# zero_board.net
KiCad netlist of a schematic drawn in EAGLE
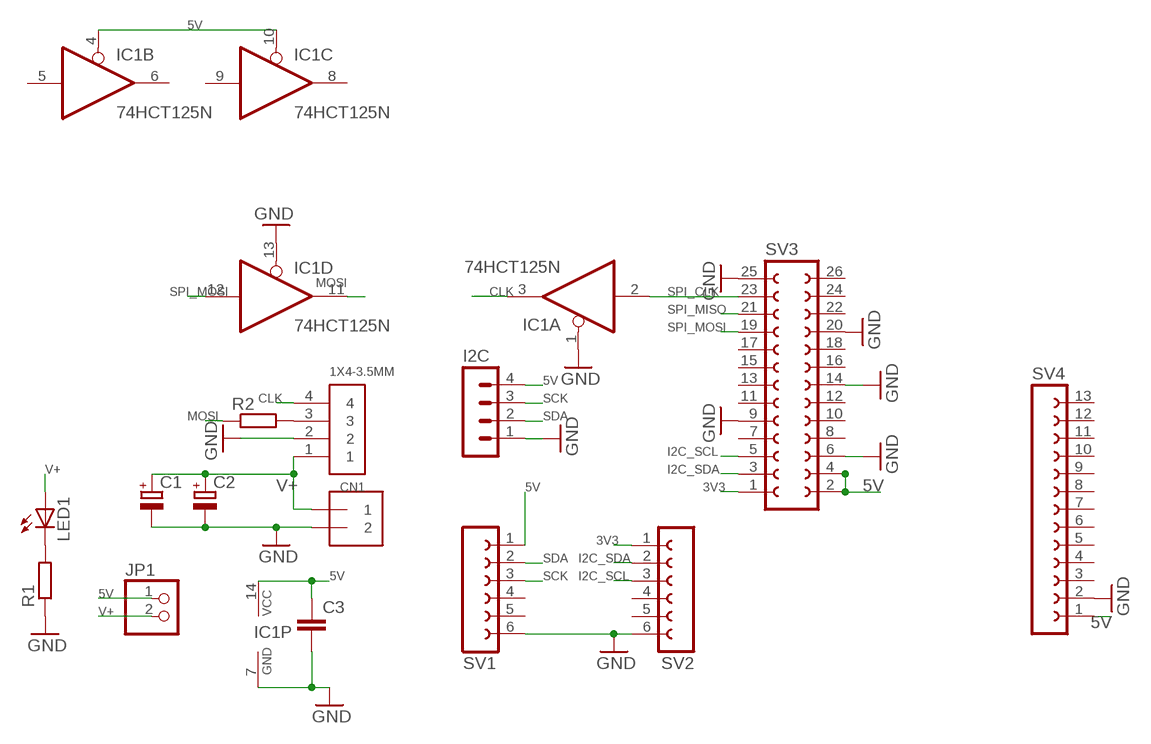
[diagram p0: schematic, sheet 1]

(export (version "E")
  (design (tool "Eeschema 10.0.6"))
  (components
    (comp (ref "C1")
      (value "CPOL-EUE5-6")
      (footprint "eagle-import:E5-6")
      (libsource (lib "eagle-import") (part "CPOL-EUE5-6"))
    )
    (comp (ref "C2")
      (value "CPOL-EUE5-6")
      (footprint "eagle-import:E5-6")
      (libsource (lib "eagle-import") (part "CPOL-EUE5-6"))
    )
    (comp (ref "C3")
      (value "C-EU050-024X044")
      (footprint "eagle-import:C050-024X044")
      (libsource (lib "eagle-import") (part "C-EU050-024X044"))
    )
    (comp (ref "CN1")
      (value "1X4-3.5MM")
      (footprint "eagle-import:1X04-3.5MM")
      (libsource (lib "eagle-import") (part "1X4-3.5MM"))
    )
    (comp (ref "I2C")
      (value "MA04-1")
      (footprint "eagle-import:MA04-1")
      (libsource (lib "eagle-import") (part "MA04-1"))
    )
    (comp (ref "IC1")
      (value "74HCT125N")
      (footprint "eagle-import:DIL14")
      (libsource (lib "eagle-import") (part "74125NHCT"))
    )
    (comp (ref "J1")
      (value "1X2-3.5MM")
      (footprint "eagle-import:1X2-3.5MM")
      (libsource (lib "eagle-import") (part "1X2-3.5MM"))
    )
    (comp (ref "JP1")
      (value "PINHD-1X2")
      (footprint "eagle-import:1X02")
      (libsource (lib "eagle-import") (part "PINHD-1X2"))
    )
    (comp (ref "LED1")
      (value "LED3MM")
      (footprint "eagle-import:LED3MM")
      (libsource (lib "eagle-import") (part "LED3MM"))
    )
    (comp (ref "R1")
      (value "R-EU_0204/5")
      (footprint "eagle-import:0204_5")
      (libsource (lib "eagle-import") (part "R-EU_0204/5"))
    )
    (comp (ref "R2")
      (value "R-EU_0204/5")
      (footprint "eagle-import:0204_5")
      (libsource (lib "eagle-import") (part "R-EU_0204/5"))
    )
    (comp (ref "SV1")
      (value "FE06-1")
      (footprint "eagle-import:FE06")
      (libsource (lib "eagle-import") (part "FE06-1"))
    )
    (comp (ref "SV2")
      (value "FE06-1")
      (footprint "eagle-import:FE06")
      (libsource (lib "eagle-import") (part "FE06-1"))
    )
    (comp (ref "SV3")
      (value "FE13-2")
      (footprint "eagle-import:FE13-2")
      (libsource (lib "eagle-import") (part "FE13-2"))
    )
    (comp (ref "SV4")
      (value "FE13-1")
      (footprint "eagle-import:FE13")
      (libsource (lib "eagle-import") (part "FE13-1"))
    )
  )
  (nets
    (net (code "1") (name "/3V3") (class "Default")
      (node (ref "SV2") (pin "1") (pinfunction "1_1") (pintype "passive"))
      (node (ref "SV3") (pin "1") (pinfunction "1_1") (pintype "passive"))
    )
    (net (code "2") (name "/5V") (class "Default")
      (node (ref "C3") (pin "1") (pinfunction "1_1") (pintype "passive"))
      (node (ref "I2C") (pin "4") (pinfunction "4_4") (pintype "passive"))
      (node (ref "IC1") (pin "10") (pinfunction "OE_10") (pintype "input"))
      (node (ref "IC1") (pin "14") (pinfunction "VCC_14") (pintype "power_in"))
      (node (ref "IC1") (pin "4") (pinfunction "OE_4") (pintype "input"))
      (node (ref "JP1") (pin "1") (pinfunction "1_1") (pintype "passive"))
      (node (ref "SV1") (pin "1") (pinfunction "1_1") (pintype "passive"))
      (node (ref "SV3") (pin "2") (pinfunction "2_2") (pintype "passive"))
      (node (ref "SV3") (pin "4") (pinfunction "4_4") (pintype "passive"))
      (node (ref "SV4") (pin "1") (pinfunction "1_1") (pintype "passive"))
    )
    (net (code "3") (name "/CLK") (class "Default")
      (node (ref "CN1") (pin "4") (pinfunction "4_4") (pintype "bidirectional"))
      (node (ref "IC1") (pin "3") (pinfunction "O_3") (pintype "tri_state"))
    )
    (net (code "4") (name "/I2C_SCL") (class "Default")
      (node (ref "SV2") (pin "3") (pinfunction "3_3") (pintype "passive"))
      (node (ref "SV3") (pin "5") (pinfunction "5_5") (pintype "passive"))
    )
    (net (code "5") (name "/I2C_SDA") (class "Default")
      (node (ref "SV2") (pin "2") (pinfunction "2_2") (pintype "passive"))
      (node (ref "SV3") (pin "3") (pinfunction "3_3") (pintype "passive"))
    )
    (net (code "6") (name "/MOSI") (class "Default")
      (node (ref "IC1") (pin "11") (pinfunction "O_11") (pintype "tri_state"))
      (node (ref "R2") (pin "1") (pinfunction "1_1") (pintype "passive"))
    )
    (net (code "7") (name "/SCK") (class "Default")
      (node (ref "I2C") (pin "3") (pinfunction "3_3") (pintype "passive"))
      (node (ref "SV1") (pin "3") (pinfunction "3_3") (pintype "passive"))
    )
    (net (code "8") (name "/SDA") (class "Default")
      (node (ref "I2C") (pin "2") (pinfunction "2_2") (pintype "passive"))
      (node (ref "SV1") (pin "2") (pinfunction "2_2") (pintype "passive"))
    )
    (net (code "9") (name "/SPI_CLK") (class "Default")
      (node (ref "IC1") (pin "2") (pinfunction "I_2") (pintype "input"))
      (node (ref "SV3") (pin "23") (pinfunction "23_23") (pintype "passive"))
    )
    (net (code "10") (name "/SPI_MISO") (class "Default")
      (node (ref "SV3") (pin "21") (pinfunction "21_21") (pintype "passive"))
    )
    (net (code "11") (name "/SPI_MOSI") (class "Default")
      (node (ref "IC1") (pin "12") (pinfunction "I_12") (pintype "input"))
      (node (ref "SV3") (pin "19") (pinfunction "19_19") (pintype "passive"))
    )
    (net (code "12") (name "/V+") (class "Default")
      (node (ref "C1") (pin "+") (pinfunction "+_+") (pintype "passive"))
      (node (ref "C2") (pin "+") (pinfunction "+_+") (pintype "passive"))
      (node (ref "CN1") (pin "1") (pinfunction "1_1") (pintype "bidirectional"))
      (node (ref "J1") (pin "1") (pinfunction "1_1") (pintype "passive"))
      (node (ref "JP1") (pin "2") (pinfunction "2_2") (pintype "passive"))
      (node (ref "LED1") (pin "A") (pinfunction "A_A") (pintype "passive"))
    )
    (net (code "13") (name "GND") (class "Default")
      (node (ref "C1") (pin "-") (pinfunction "-_-") (pintype "passive"))
      (node (ref "C2") (pin "-") (pinfunction "-_-") (pintype "passive"))
      (node (ref "C3") (pin "2") (pinfunction "2_2") (pintype "passive"))
      (node (ref "CN1") (pin "2") (pinfunction "2_2") (pintype "bidirectional"))
      (node (ref "I2C") (pin "1") (pinfunction "1_1") (pintype "passive"))
      (node (ref "IC1") (pin "1") (pinfunction "OE_1") (pintype "input"))
      (node (ref "IC1") (pin "13") (pinfunction "OE_13") (pintype "input"))
      (node (ref "IC1") (pin "7") (pinfunction "GND_7") (pintype "power_in"))
      (node (ref "J1") (pin "2") (pinfunction "2_2") (pintype "passive"))
      (node (ref "R1") (pin "1") (pinfunction "1_1") (pintype "passive"))
      (node (ref "SV1") (pin "6") (pinfunction "6_6") (pintype "passive"))
      (node (ref "SV2") (pin "6") (pinfunction "6_6") (pintype "passive"))
      (node (ref "SV3") (pin "14") (pinfunction "14_14") (pintype "passive"))
      (node (ref "SV3") (pin "20") (pinfunction "20_20") (pintype "passive"))
      (node (ref "SV3") (pin "25") (pinfunction "25_25") (pintype "passive"))
      (node (ref "SV3") (pin "6") (pinfunction "6_6") (pintype "passive"))
      (node (ref "SV3") (pin "9") (pinfunction "9_9") (pintype "passive"))
      (node (ref "SV4") (pin "2") (pinfunction "2_2") (pintype "passive"))
    )
    (net (code "14") (name "Net-(CN1-Pad3)") (class "Default")
      (node (ref "CN1") (pin "3") (pinfunction "3_3") (pintype "bidirectional"))
      (node (ref "R2") (pin "2") (pinfunction "2_2") (pintype "passive"))
    )
    (net (code "15") (name "Net-(LED1-C)") (class "Default")
      (node (ref "LED1") (pin "K") (pinfunction "C_K") (pintype "passive"))
      (node (ref "R1") (pin "2") (pinfunction "2_2") (pintype "passive"))
    )
    (net (code "16") (name "unconnected-(IC1B-I-Pad5)") (class "Default")
      (node (ref "IC1") (pin "5") (pinfunction "I_5") (pintype "input"))
    )
    (net (code "17") (name "unconnected-(IC1B-O-Pad6)") (class "Default")
      (node (ref "IC1") (pin "6") (pinfunction "O_6") (pintype "tri_state"))
    )
    (net (code "18") (name "unconnected-(IC1C-I-Pad9)") (class "Default")
      (node (ref "IC1") (pin "9") (pinfunction "I_9") (pintype "input"))
    )
    (net (code "19") (name "unconnected-(IC1C-O-Pad8)") (class "Default")
      (node (ref "IC1") (pin "8") (pinfunction "O_8") (pintype "tri_state"))
    )
    (net (code "20") (name "unconnected-(SV1-Pad4)") (class "Default")
      (node (ref "SV1") (pin "4") (pinfunction "4_4") (pintype "passive"))
    )
    (net (code "21") (name "unconnected-(SV1-Pad5)") (class "Default")
      (node (ref "SV1") (pin "5") (pinfunction "5_5") (pintype "passive"))
    )
    (net (code "22") (name "unconnected-(SV2-Pad4)") (class "Default")
      (node (ref "SV2") (pin "4") (pinfunction "4_4") (pintype "passive"))
    )
    (net (code "23") (name "unconnected-(SV2-Pad5)") (class "Default")
      (node (ref "SV2") (pin "5") (pinfunction "5_5") (pintype "passive"))
    )
    (net (code "24") (name "unconnected-(SV3-Pad7)") (class "Default")
      (node (ref "SV3") (pin "7") (pinfunction "7_7") (pintype "passive"))
    )
    (net (code "25") (name "unconnected-(SV3-Pad8)") (class "Default")
      (node (ref "SV3") (pin "8") (pinfunction "8_8") (pintype "passive"))
    )
    (net (code "26") (name "unconnected-(SV3-Pad10)") (class "Default")
      (node (ref "SV3") (pin "10") (pinfunction "10_10") (pintype "passive"))
    )
    (net (code "27") (name "unconnected-(SV3-Pad11)") (class "Default")
      (node (ref "SV3") (pin "11") (pinfunction "11_11") (pintype "passive"))
    )
    (net (code "28") (name "unconnected-(SV3-Pad12)") (class "Default")
      (node (ref "SV3") (pin "12") (pinfunction "12_12") (pintype "passive"))
    )
    (net (code "29") (name "unconnected-(SV3-Pad13)") (class "Default")
      (node (ref "SV3") (pin "13") (pinfunction "13_13") (pintype "passive"))
    )
    (net (code "30") (name "unconnected-(SV3-Pad15)") (class "Default")
      (node (ref "SV3") (pin "15") (pinfunction "15_15") (pintype "passive"))
    )
    (net (code "31") (name "unconnected-(SV3-Pad16)") (class "Default")
      (node (ref "SV3") (pin "16") (pinfunction "16_16") (pintype "passive"))
    )
    (net (code "32") (name "unconnected-(SV3-Pad17)") (class "Default")
      (node (ref "SV3") (pin "17") (pinfunction "17_17") (pintype "passive"))
    )
    (net (code "33") (name "unconnected-(SV3-Pad18)") (class "Default")
      (node (ref "SV3") (pin "18") (pinfunction "18_18") (pintype "passive"))
    )
    (net (code "34") (name "unconnected-(SV3-Pad22)") (class "Default")
      (node (ref "SV3") (pin "22") (pinfunction "22_22") (pintype "passive"))
    )
    (net (code "35") (name "unconnected-(SV3-Pad24)") (class "Default")
      (node (ref "SV3") (pin "24") (pinfunction "24_24") (pintype "passive"))
    )
    (net (code "36") (name "unconnected-(SV3-Pad26)") (class "Default")
      (node (ref "SV3") (pin "26") (pinfunction "26_26") (pintype "passive"))
    )
    (net (code "37") (name "unconnected-(SV4-Pad3)") (class "Default")
      (node (ref "SV4") (pin "3") (pinfunction "3_3") (pintype "passive"))
    )
    (net (code "38") (name "unconnected-(SV4-Pad4)") (class "Default")
      (node (ref "SV4") (pin "4") (pinfunction "4_4") (pintype "passive"))
    )
    (net (code "39") (name "unconnected-(SV4-Pad5)") (class "Default")
      (node (ref "SV4") (pin "5") (pinfunction "5_5") (pintype "passive"))
    )
    (net (code "40") (name "unconnected-(SV4-Pad6)") (class "Default")
      (node (ref "SV4") (pin "6") (pinfunction "6_6") (pintype "passive"))
    )
    (net (code "41") (name "unconnected-(SV4-Pad7)") (class "Default")
      (node (ref "SV4") (pin "7") (pinfunction "7_7") (pintype "passive"))
    )
    (net (code "42") (name "unconnected-(SV4-Pad8)") (class "Default")
      (node (ref "SV4") (pin "8") (pinfunction "8_8") (pintype "passive"))
    )
    (net (code "43") (name "unconnected-(SV4-Pad9)") (class "Default")
      (node (ref "SV4") (pin "9") (pinfunction "9_9") (pintype "passive"))
    )
    (net (code "44") (name "unconnected-(SV4-Pad10)") (class "Default")
      (node (ref "SV4") (pin "10") (pinfunction "10_10") (pintype "passive"))
    )
    (net (code "45") (name "unconnected-(SV4-Pad11)") (class "Default")
      (node (ref "SV4") (pin "11") (pinfunction "11_11") (pintype "passive"))
    )
    (net (code "46") (name "unconnected-(SV4-Pad12)") (class "Default")
      (node (ref "SV4") (pin "12") (pinfunction "12_12") (pintype "passive"))
    )
    (net (code "47") (name "unconnected-(SV4-Pad13)") (class "Default")
      (node (ref "SV4") (pin "13") (pinfunction "13_13") (pintype "passive"))
    )
  )
)
